# imu.net
KiCad netlist of a schematic drawn in EasyEDA Pro
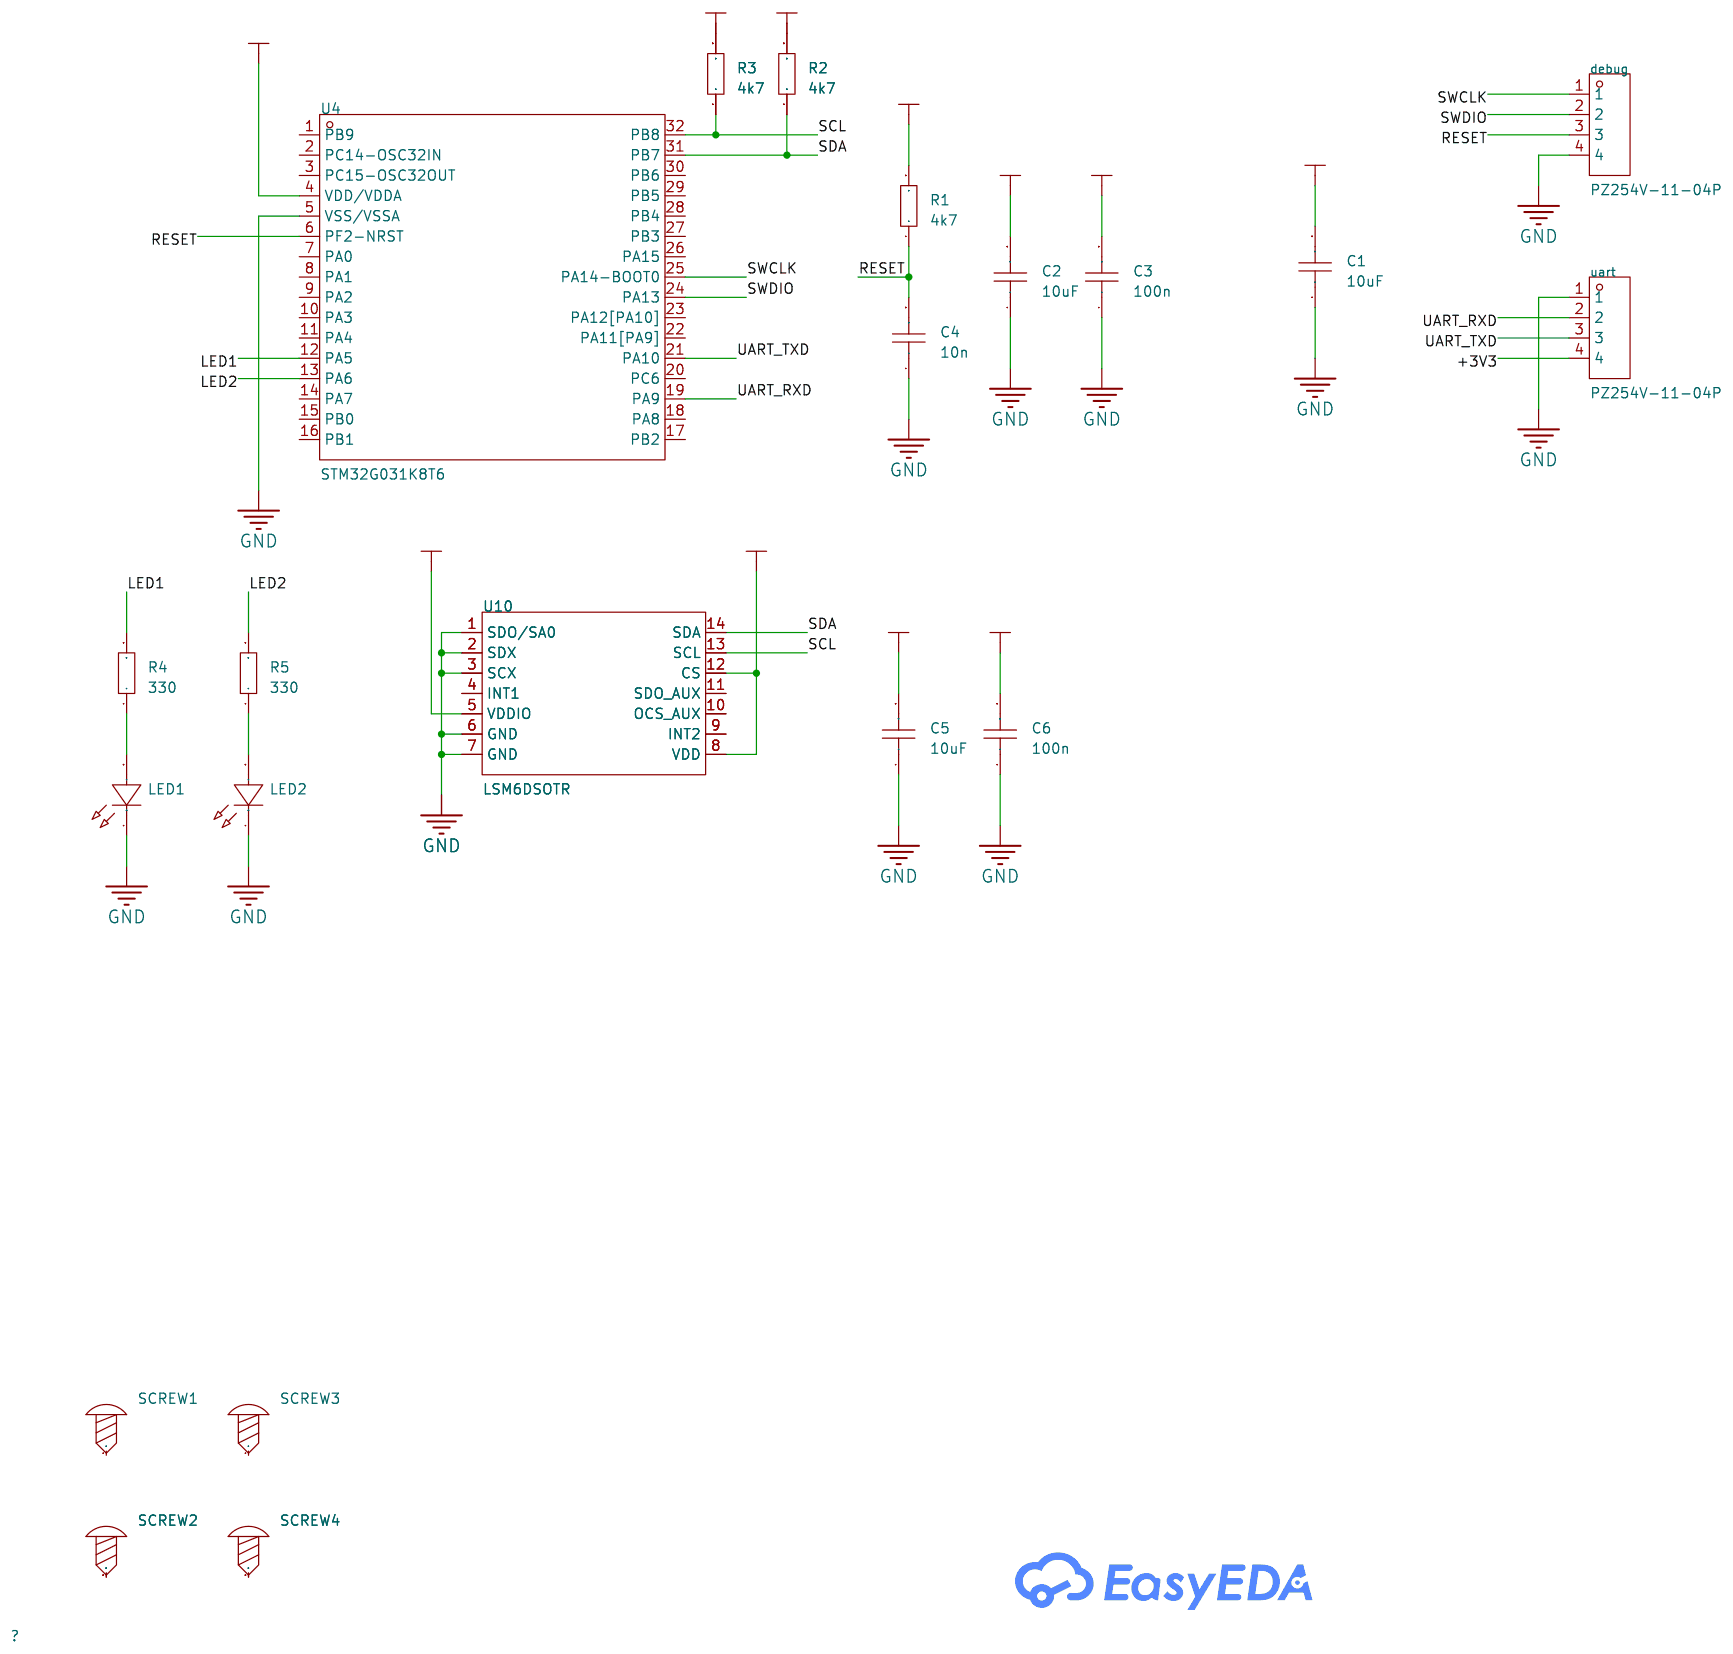
[diagram p0: schematic sheet]

(export (version "E")
  (design (tool "Eeschema 10.0.6"))
  (components
    (comp (ref "C1")
      (value "10uF")
      (footprint "easyedapro:C0805")
      (description "Capacitance:10uF Tolerance:±10% Tolerance:±10% Voltage Rating:25V Temperature Coefficient:X5R")
      (fields
        (field (name "Manufacturer Part") "CL21A106KAYNNNE")
        (field (name "Manufacturer") "SAMSUNG(三星)")
      )
      (libsource (lib "easyedapro") (part "CL21A106KAYNNNE"))
    )
    (comp (ref "C2")
      (value "10uF")
      (footprint "easyedapro:C0805")
      (description "Capacitance:10uF Tolerance:±10% Tolerance:±10% Voltage Rating:25V Temperature Coefficient:X5R")
      (fields
        (field (name "Manufacturer Part") "CL21A106KAYNNNE")
        (field (name "Manufacturer") "SAMSUNG(三星)")
      )
      (libsource (lib "easyedapro") (part "CL21A106KAYNNNE"))
    )
    (comp (ref "C3")
      (value "10uF")
      (footprint "easyedapro:C0805")
      (description "Capacitance:10uF Tolerance:±10% Tolerance:±10% Voltage Rating:25V Temperature Coefficient:X5R")
      (fields
        (field (name "Manufacturer Part") "CL21A106KAYNNNE")
        (field (name "Manufacturer") "SAMSUNG(三星)")
      )
      (libsource (lib "easyedapro") (part "CL21A106KAYNNNE"))
    )
    (comp (ref "C4")
      (value "10uF")
      (footprint "easyedapro:C0805")
      (description "Capacitance:10uF Tolerance:±10% Tolerance:±10% Voltage Rating:25V Temperature Coefficient:X5R")
      (fields
        (field (name "Manufacturer Part") "CL21A106KAYNNNE")
        (field (name "Manufacturer") "SAMSUNG(三星)")
      )
      (libsource (lib "easyedapro") (part "CL21A106KAYNNNE"))
    )
    (comp (ref "C5")
      (value "10uF")
      (footprint "easyedapro:C0805")
      (description "Capacitance:10uF Tolerance:±10% Tolerance:±10% Voltage Rating:25V Temperature Coefficient:X5R")
      (fields
        (field (name "Manufacturer Part") "CL21A106KAYNNNE")
        (field (name "Manufacturer") "SAMSUNG(三星)")
      )
      (libsource (lib "easyedapro") (part "CL21A106KAYNNNE"))
    )
    (comp (ref "C6")
      (value "10uF")
      (footprint "easyedapro:C0805")
      (description "Capacitance:10uF Tolerance:±10% Tolerance:±10% Voltage Rating:25V Temperature Coefficient:X5R")
      (fields
        (field (name "Manufacturer Part") "CL21A106KAYNNNE")
        (field (name "Manufacturer") "SAMSUNG(三星)")
      )
      (libsource (lib "easyedapro") (part "CL21A106KAYNNNE"))
    )
    (comp (ref "debug")
      (value "PZ254V-11-04P")
      (footprint "easyedapro:HDR-TH_4P-P2.54-V-M")
      (fields (field (name "Manufacturer") "XFCN(兴飞)"))
      (libsource (lib "easyedapro") (part "PZ254V-11-04P_C2691448"))
    )
    (comp (ref "LED1")
      (value "P2-1206RTCS2-0.9T-F")
      (footprint "easyedapro:LED-SMD_L3.2-W1.6-P2-1206RTCS2-0.9T-F")
      (fields (field (name "Manufacturer") "TUOZHAN(拓展光电)"))
      (libsource (lib "easyedapro") (part "P2-1206RTCS2-0.9T-F"))
    )
    (comp (ref "LED2")
      (value "P2-1206RTCS2-0.9T-F")
      (footprint "easyedapro:LED-SMD_L3.2-W1.6-P2-1206RTCS2-0.9T-F")
      (fields (field (name "Manufacturer") "TUOZHAN(拓展光电)"))
      (libsource (lib "easyedapro") (part "P2-1206RTCS2-0.9T-F"))
    )
    (comp (ref "R1")
      (value "10kΩ")
      (footprint "easyedapro:R0805")
      (fields
        (field (name "Manufacturer Part") "0805W8F1002T5E")
        (field (name "Manufacturer") "UNI-ROYAL(厚声)")
      )
      (libsource (lib "easyedapro") (part "0805W8F1002T5E"))
    )
    (comp (ref "R2")
      (value "10kΩ")
      (footprint "easyedapro:R0805")
      (fields
        (field (name "Manufacturer Part") "0805W8F1002T5E")
        (field (name "Manufacturer") "UNI-ROYAL(厚声)")
      )
      (libsource (lib "easyedapro") (part "0805W8F1002T5E"))
    )
    (comp (ref "R3")
      (value "10kΩ")
      (footprint "easyedapro:R0805")
      (fields
        (field (name "Manufacturer Part") "0805W8F1002T5E")
        (field (name "Manufacturer") "UNI-ROYAL(厚声)")
      )
      (libsource (lib "easyedapro") (part "0805W8F1002T5E"))
    )
    (comp (ref "R4")
      (value "10kΩ")
      (footprint "easyedapro:R0805")
      (fields
        (field (name "Manufacturer Part") "0805W8F1002T5E")
        (field (name "Manufacturer") "UNI-ROYAL(厚声)")
      )
      (libsource (lib "easyedapro") (part "0805W8F1002T5E"))
    )
    (comp (ref "R5")
      (value "10kΩ")
      (footprint "easyedapro:R0805")
      (fields
        (field (name "Manufacturer Part") "0805W8F1002T5E")
        (field (name "Manufacturer") "UNI-ROYAL(厚声)")
      )
      (libsource (lib "easyedapro") (part "0805W8F1002T5E"))
    )
    (comp (ref "SCREW1")
      (value "~")
      (footprint "easyedapro:Screw-Hole-M3")
      (libsource (lib "easyedapro") (part "Screw-Hole"))
    )
    (comp (ref "SCREW2")
      (value "~")
      (footprint "easyedapro:Screw-Hole-M3")
      (libsource (lib "easyedapro") (part "Screw-Hole"))
    )
    (comp (ref "SCREW3")
      (value "~")
      (footprint "easyedapro:Screw-Hole-M3")
      (libsource (lib "easyedapro") (part "Screw-Hole"))
    )
    (comp (ref "SCREW4")
      (value "~")
      (footprint "easyedapro:Screw-Hole-M3")
      (libsource (lib "easyedapro") (part "Screw-Hole"))
    )
    (comp (ref "U4")
      (value "STM32G031K8T6")
      (footprint "easyedapro:LQFP-32_L7.0-W7.0-P0.80-LS9.0-BL")
      (fields (field (name "Manufacturer") "ST(意法半导体)"))
      (libsource (lib "easyedapro") (part "STM32G031K8T6"))
    )
    (comp (ref "U10")
      (value "LSM6DSOTR")
      (footprint "easyedapro:LGA-14_L3.0-W2.5-P0.50-TL")
      (fields (field (name "Manufacturer") "ST(意法半导体)"))
      (libsource (lib "easyedapro") (part "LSM6DSOTR"))
    )
    (comp (ref "uart")
      (value "PZ254V-11-04P")
      (footprint "easyedapro:HDR-TH_4P-P2.54-V-M")
      (fields (field (name "Manufacturer") "XFCN(兴飞)"))
      (libsource (lib "easyedapro") (part "PZ254V-11-04P_C2691448"))
    )
  )
  (nets
    (net (code "1") (name "+3V3") (class "Default")
      (node (ref "C1") (pin "2") (pinfunction "2_2") (pintype "unspecified"))
      (node (ref "C2") (pin "2") (pinfunction "2_2") (pintype "unspecified"))
      (node (ref "C3") (pin "2") (pinfunction "2_2") (pintype "unspecified"))
      (node (ref "C5") (pin "2") (pinfunction "2_2") (pintype "unspecified"))
      (node (ref "C6") (pin "2") (pinfunction "2_2") (pintype "unspecified"))
      (node (ref "R1") (pin "2") (pinfunction "2_2") (pintype "input"))
      (node (ref "R2") (pin "2") (pinfunction "2_2") (pintype "input"))
      (node (ref "R3") (pin "2") (pinfunction "2_2") (pintype "input"))
      (node (ref "U10") (pin "12") (pinfunction "CS_12") (pintype "unspecified"))
      (node (ref "U10") (pin "5") (pinfunction "VDDIO_5") (pintype "unspecified"))
      (node (ref "U10") (pin "8") (pinfunction "VDD_8") (pintype "unspecified"))
      (node (ref "U4") (pin "4") (pinfunction "VDD/VDDA_4") (pintype "unspecified"))
      (node (ref "uart") (pin "4") (pinfunction "4_4") (pintype "input"))
    )
    (net (code "2") (name "/LED1") (class "Default")
      (node (ref "R4") (pin "2") (pinfunction "2_2") (pintype "input"))
      (node (ref "U4") (pin "12") (pinfunction "PA5_12") (pintype "unspecified"))
    )
    (net (code "3") (name "/LED2") (class "Default")
      (node (ref "R5") (pin "2") (pinfunction "2_2") (pintype "input"))
      (node (ref "U4") (pin "13") (pinfunction "PA6_13") (pintype "unspecified"))
    )
    (net (code "4") (name "/RESET") (class "Default")
      (node (ref "C4") (pin "2") (pinfunction "2_2") (pintype "unspecified"))
      (node (ref "R1") (pin "1") (pinfunction "1_1") (pintype "input"))
      (node (ref "U4") (pin "6") (pinfunction "PF2-NRST_6") (pintype "unspecified"))
      (node (ref "debug") (pin "3") (pinfunction "3_3") (pintype "input"))
    )
    (net (code "5") (name "/SCL") (class "Default")
      (node (ref "R3") (pin "1") (pinfunction "1_1") (pintype "input"))
      (node (ref "U10") (pin "13") (pinfunction "SCL_13") (pintype "unspecified"))
      (node (ref "U4") (pin "32") (pinfunction "PB8_32") (pintype "unspecified"))
    )
    (net (code "6") (name "/SDA") (class "Default")
      (node (ref "R2") (pin "1") (pinfunction "1_1") (pintype "input"))
      (node (ref "U10") (pin "14") (pinfunction "SDA_14") (pintype "unspecified"))
      (node (ref "U4") (pin "31") (pinfunction "PB7_31") (pintype "unspecified"))
    )
    (net (code "7") (name "/SWCLK") (class "Default")
      (node (ref "U4") (pin "25") (pinfunction "PA14-BOOT0_25") (pintype "unspecified"))
      (node (ref "debug") (pin "1") (pinfunction "1_1") (pintype "input"))
    )
    (net (code "8") (name "/SWDIO") (class "Default")
      (node (ref "U4") (pin "24") (pinfunction "PA13_24") (pintype "unspecified"))
      (node (ref "debug") (pin "2") (pinfunction "2_2") (pintype "input"))
    )
    (net (code "9") (name "/UART_RXD") (class "Default")
      (node (ref "U4") (pin "19") (pinfunction "PA9_19") (pintype "unspecified"))
      (node (ref "uart") (pin "2") (pinfunction "2_2") (pintype "input"))
    )
    (net (code "10") (name "/UART_TXD") (class "Default")
      (node (ref "U4") (pin "21") (pinfunction "PA10_21") (pintype "unspecified"))
      (node (ref "uart") (pin "3") (pinfunction "3_3") (pintype "input"))
    )
    (net (code "11") (name "GND") (class "Default")
      (node (ref "C1") (pin "1") (pinfunction "1_1") (pintype "unspecified"))
      (node (ref "C2") (pin "1") (pinfunction "1_1") (pintype "unspecified"))
      (node (ref "C3") (pin "1") (pinfunction "1_1") (pintype "unspecified"))
      (node (ref "C4") (pin "1") (pinfunction "1_1") (pintype "unspecified"))
      (node (ref "C5") (pin "1") (pinfunction "1_1") (pintype "unspecified"))
      (node (ref "C6") (pin "1") (pinfunction "1_1") (pintype "unspecified"))
      (node (ref "LED1") (pin "1") (pinfunction "C_1") (pintype "unspecified"))
      (node (ref "LED2") (pin "1") (pinfunction "C_1") (pintype "unspecified"))
      (node (ref "U10") (pin "1") (pinfunction "SDO/SA0_1") (pintype "unspecified"))
      (node (ref "U10") (pin "2") (pinfunction "SDX_2") (pintype "unspecified"))
      (node (ref "U10") (pin "3") (pinfunction "SCX_3") (pintype "unspecified"))
      (node (ref "U10") (pin "6") (pinfunction "GND_6") (pintype "unspecified"))
      (node (ref "U10") (pin "7") (pinfunction "GND_7") (pintype "unspecified"))
      (node (ref "U4") (pin "5") (pinfunction "VSS/VSSA_5") (pintype "unspecified"))
      (node (ref "debug") (pin "4") (pinfunction "4_4") (pintype "input"))
      (node (ref "uart") (pin "1") (pinfunction "1_1") (pintype "input"))
    )
    (net (code "12") (name "Net-(LED1-A)") (class "Default")
      (node (ref "LED1") (pin "2") (pinfunction "A_2") (pintype "unspecified"))
      (node (ref "R4") (pin "1") (pinfunction "1_1") (pintype "input"))
    )
    (net (code "13") (name "Net-(LED2-A)") (class "Default")
      (node (ref "LED2") (pin "2") (pinfunction "A_2") (pintype "unspecified"))
      (node (ref "R5") (pin "1") (pinfunction "1_1") (pintype "input"))
    )
    (net (code "14") (name "unconnected-(SCREW1-Pad1)") (class "Default")
      (node (ref "SCREW1") (pin "1") (pinfunction "1_1") (pintype "input"))
    )
    (net (code "15") (name "unconnected-(SCREW2-Pad1)") (class "Default")
      (node (ref "SCREW2") (pin "1") (pinfunction "1_1") (pintype "input"))
    )
    (net (code "16") (name "unconnected-(SCREW3-Pad1)") (class "Default")
      (node (ref "SCREW3") (pin "1") (pinfunction "1_1") (pintype "input"))
    )
    (net (code "17") (name "unconnected-(SCREW4-Pad1)") (class "Default")
      (node (ref "SCREW4") (pin "1") (pinfunction "1_1") (pintype "input"))
    )
    (net (code "18") (name "unconnected-(U4-PA0-Pad7)") (class "Default")
      (node (ref "U4") (pin "7") (pinfunction "PA0_7") (pintype "unspecified"))
    )
    (net (code "19") (name "unconnected-(U4-PA1-Pad8)") (class "Default")
      (node (ref "U4") (pin "8") (pinfunction "PA1_8") (pintype "unspecified"))
    )
    (net (code "20") (name "unconnected-(U4-PA2-Pad9)") (class "Default")
      (node (ref "U4") (pin "9") (pinfunction "PA2_9") (pintype "unspecified"))
    )
    (net (code "21") (name "unconnected-(U4-PA3-Pad10)") (class "Default")
      (node (ref "U4") (pin "10") (pinfunction "PA3_10") (pintype "unspecified"))
    )
    (net (code "22") (name "unconnected-(U4-PA4-Pad11)") (class "Default")
      (node (ref "U4") (pin "11") (pinfunction "PA4_11") (pintype "unspecified"))
    )
    (net (code "23") (name "unconnected-(U4-PA7-Pad14)") (class "Default")
      (node (ref "U4") (pin "14") (pinfunction "PA7_14") (pintype "unspecified"))
    )
    (net (code "24") (name "unconnected-(U4-PA8-Pad18)") (class "Default")
      (node (ref "U4") (pin "18") (pinfunction "PA8_18") (pintype "unspecified"))
    )
    (net (code "25") (name "unconnected-(U4-PA11[PA9]-Pad22)") (class "Default")
      (node (ref "U4") (pin "22") (pinfunction "PA11[PA9]_22") (pintype "unspecified"))
    )
    (net (code "26") (name "unconnected-(U4-PA12[PA10]-Pad23)") (class "Default")
      (node (ref "U4") (pin "23") (pinfunction "PA12[PA10]_23") (pintype "unspecified"))
    )
    (net (code "27") (name "unconnected-(U4-PA15-Pad26)") (class "Default")
      (node (ref "U4") (pin "26") (pinfunction "PA15_26") (pintype "unspecified"))
    )
    (net (code "28") (name "unconnected-(U4-PB0-Pad15)") (class "Default")
      (node (ref "U4") (pin "15") (pinfunction "PB0_15") (pintype "unspecified"))
    )
    (net (code "29") (name "unconnected-(U4-PB1-Pad16)") (class "Default")
      (node (ref "U4") (pin "16") (pinfunction "PB1_16") (pintype "unspecified"))
    )
    (net (code "30") (name "unconnected-(U4-PB2-Pad17)") (class "Default")
      (node (ref "U4") (pin "17") (pinfunction "PB2_17") (pintype "unspecified"))
    )
    (net (code "31") (name "unconnected-(U4-PB3-Pad27)") (class "Default")
      (node (ref "U4") (pin "27") (pinfunction "PB3_27") (pintype "unspecified"))
    )
    (net (code "32") (name "unconnected-(U4-PB4-Pad28)") (class "Default")
      (node (ref "U4") (pin "28") (pinfunction "PB4_28") (pintype "unspecified"))
    )
    (net (code "33") (name "unconnected-(U4-PB5-Pad29)") (class "Default")
      (node (ref "U4") (pin "29") (pinfunction "PB5_29") (pintype "unspecified"))
    )
    (net (code "34") (name "unconnected-(U4-PB6-Pad30)") (class "Default")
      (node (ref "U4") (pin "30") (pinfunction "PB6_30") (pintype "unspecified"))
    )
    (net (code "35") (name "unconnected-(U4-PB9-Pad1)") (class "Default")
      (node (ref "U4") (pin "1") (pinfunction "PB9_1") (pintype "unspecified"))
    )
    (net (code "36") (name "unconnected-(U4-PC6-Pad20)") (class "Default")
      (node (ref "U4") (pin "20") (pinfunction "PC6_20") (pintype "unspecified"))
    )
    (net (code "37") (name "unconnected-(U4-PC14-OSC32IN-Pad2)") (class "Default")
      (node (ref "U4") (pin "2") (pinfunction "PC14-OSC32IN_2") (pintype "unspecified"))
    )
    (net (code "38") (name "unconnected-(U4-PC15-OSC32OUT-Pad3)") (class "Default")
      (node (ref "U4") (pin "3") (pinfunction "PC15-OSC32OUT_3") (pintype "unspecified"))
    )
    (net (code "39") (name "unconnected-(U10-INT1-Pad4)") (class "Default")
      (node (ref "U10") (pin "4") (pinfunction "INT1_4") (pintype "unspecified"))
    )
    (net (code "40") (name "unconnected-(U10-INT2-Pad9)") (class "Default")
      (node (ref "U10") (pin "9") (pinfunction "INT2_9") (pintype "unspecified"))
    )
    (net (code "41") (name "unconnected-(U10-OCS_AUX-Pad10)") (class "Default")
      (node (ref "U10") (pin "10") (pinfunction "OCS_AUX_10") (pintype "unspecified"))
    )
    (net (code "42") (name "unconnected-(U10-SDO_AUX-Pad11)") (class "Default")
      (node (ref "U10") (pin "11") (pinfunction "SDO_AUX_11") (pintype "unspecified"))
    )
  )
)
